# SH5_-_LED.net
KiCad netlist of a schematic drawn in Altium Designer
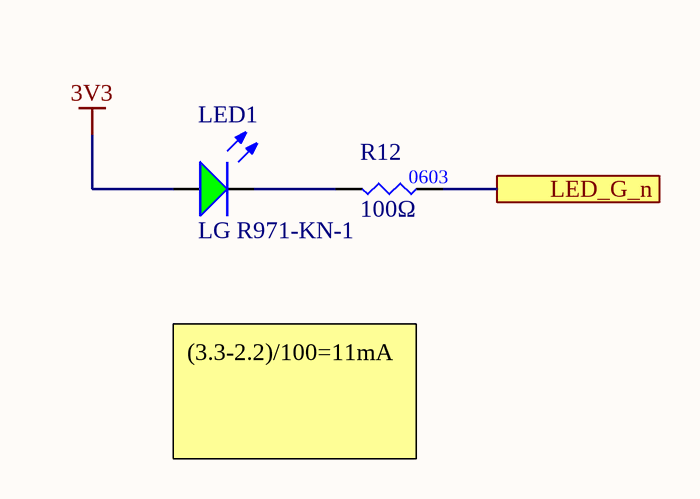
[diagram p0: SH5 - LED.SchDoc]

(export (version "E")
  (design (tool "Eeschema 10.0.6"))
  (components
    (comp (ref "LED1")
      (value "LED_GREEN")
      (footprint "LED_0805_GREEN")
      (description "LED GREEN DIFFUSED 0805 SMD")
      (fields (field (name "MANUFACTURER PART NUMBER 1") "LG R971-KN-1"))
      (libsource (lib "UWRT_Schematic_Library_2020") (part "LED_GREEN"))
    )
    (comp (ref "R12")
      (value "100Ω")
      (footprint "RES0603")
      (description "RES 100 OHM 1% 1/10W 0603")
      (fields (field (name "Comment") "RES_100Ω_0603_1%"))
      (libsource (lib "UWRT_Schematic_Library_2020") (part "RES_100Ω_0603_1%"))
    )
  )
  (nets
    (net (code "1") (name "/LED_G_n") (class "Default")
      (node (ref "R12") (pin "2") (pinfunction "2_2") (pintype "passive"))
    )
    (net (code "2") (name "3V3") (class "Default")
      (node (ref "LED1") (pin "1") (pinfunction "A_1") (pintype "passive"))
    )
    (net (code "3") (name "Net-(LED1-K)") (class "Default")
      (node (ref "LED1") (pin "2") (pinfunction "K_2") (pintype "passive"))
      (node (ref "R12") (pin "1") (pinfunction "1_1") (pintype "passive"))
    )
  )
)
